# Croduino_Nova_v2_0.net
KiCad netlist of a schematic drawn in EAGLE
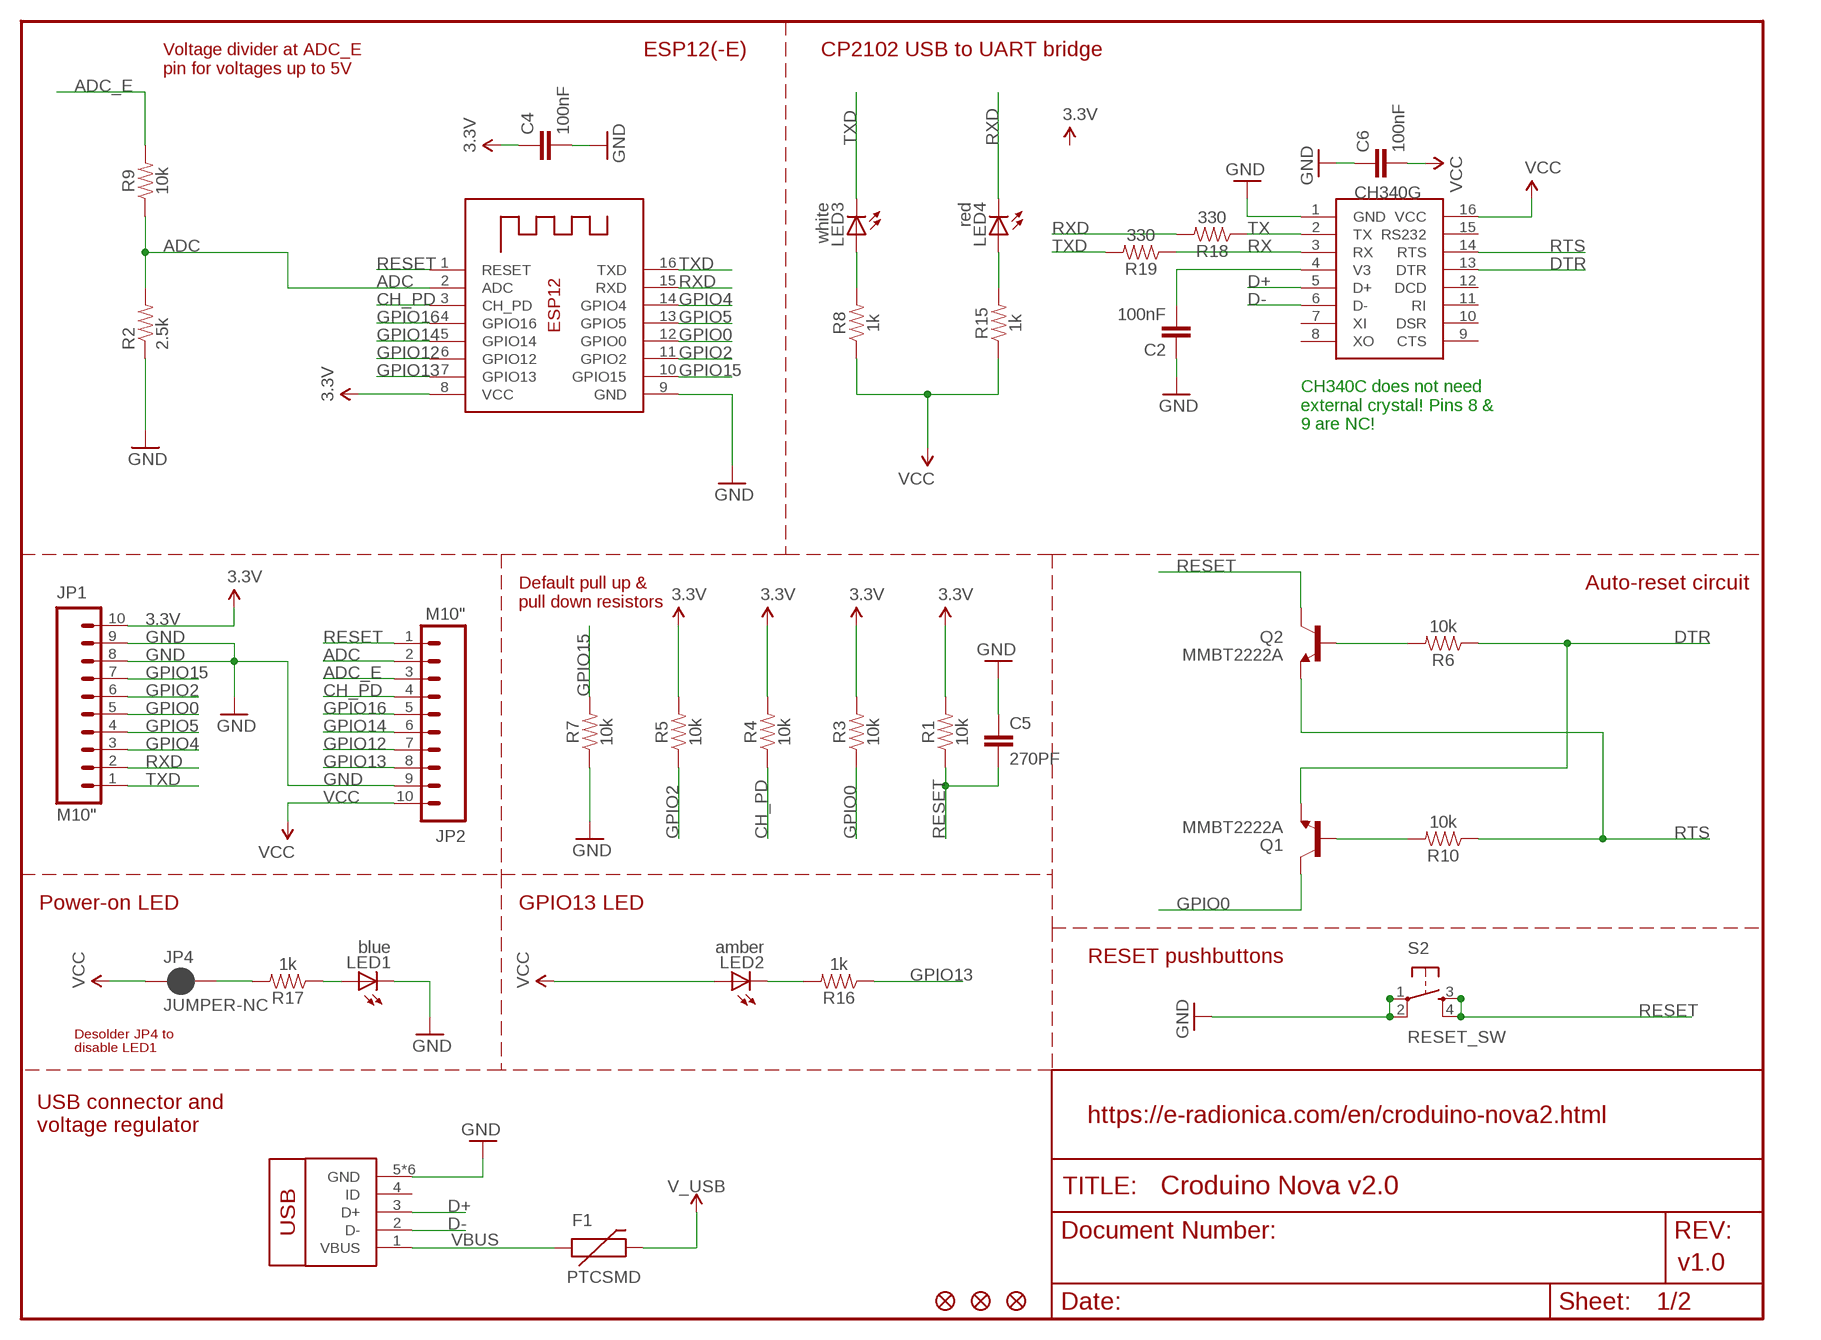
[diagram p0: schematic, sheet 1]
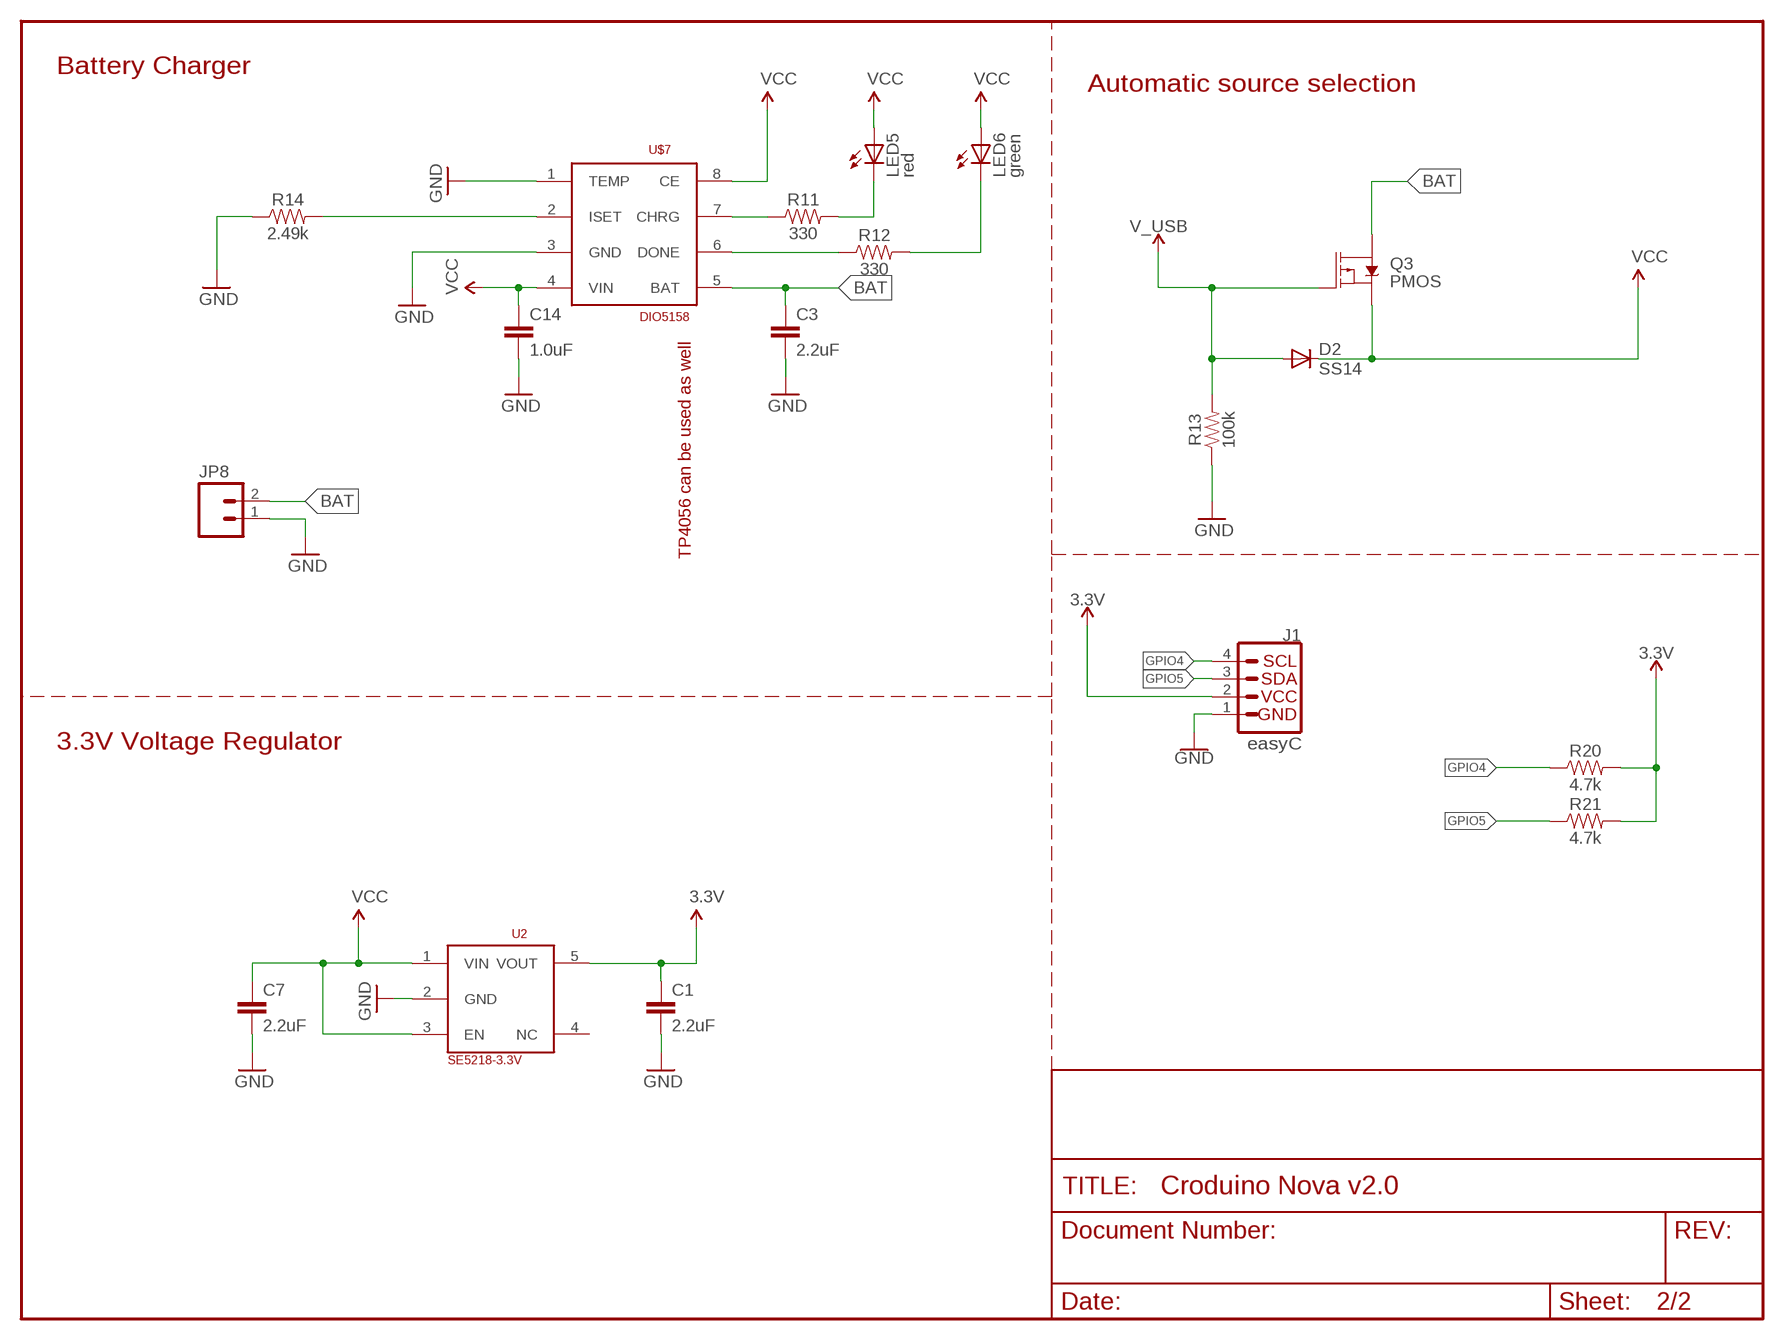
[diagram p1: schematic, sheet 2]

(export (version "E")
  (design (tool "Eeschema 10.0.6"))
  (components
    (comp (ref "C2")
      (value "100nF")
      (footprint "eagle-import:0603-CAP")
      (libsource (lib "eagle-import") (part "CAP0603-CAP"))
    )
    (comp (ref "C4")
      (value "100nF")
      (footprint "eagle-import:0603-CAP")
      (libsource (lib "eagle-import") (part "CAP0603-CAP"))
    )
    (comp (ref "C5")
      (value "270PF")
      (footprint "eagle-import:0603")
      (libsource (lib "eagle-import") (part "270PF-0603-50V-5%"))
    )
    (comp (ref "C6")
      (value "100nF")
      (footprint "eagle-import:0603-CAP")
      (libsource (lib "eagle-import") (part "CAP0603-CAP"))
    )
    (comp (ref "F1")
      (value "PTCSMD")
      (footprint "eagle-import:PTC-1206")
      (libsource (lib "eagle-import") (part "PTCSMD"))
    )
    (comp (ref "JP1")
      (value "M10\"")
      (footprint "eagle-import:1X10")
      (libsource (lib "eagle-import") (part "M10{dblquote}"))
    )
    (comp (ref "JP2")
      (value "M10\"")
      (footprint "eagle-import:1X10")
      (libsource (lib "eagle-import") (part "M10{dblquote}"))
    )
    (comp (ref "JP3")
      (value "FIDUCIAL1X2")
      (footprint "eagle-import:FIDUCIAL-1X2")
      (libsource (lib "eagle-import") (part "FIDUCIAL1X2"))
    )
    (comp (ref "JP4")
      (value "JUMPER-NC")
      (footprint "eagle-import:SMT-JUMPER_2_NC_PASTE_NO-SILK")
      (libsource (lib "eagle-import") (part "JUMPER-SMT_2_NC_PASTE_NO-SILK"))
    )
    (comp (ref "JP5")
      (value "FIDUCIAL1X2")
      (footprint "eagle-import:FIDUCIAL-1X2")
      (libsource (lib "eagle-import") (part "FIDUCIAL1X2"))
    )
    (comp (ref "JP6")
      (value "FIDUCIAL1X2")
      (footprint "eagle-import:FIDUCIAL-1X2")
      (libsource (lib "eagle-import") (part "FIDUCIAL1X2"))
    )
    (comp (ref "LED1")
      (value "blue")
      (footprint "eagle-import:CHIP-LED0805")
      (libsource (lib "eagle-import") (part "LEDCHIP-LED0805"))
    )
    (comp (ref "LED2")
      (value "amber")
      (footprint "eagle-import:CHIP-LED0805")
      (libsource (lib "eagle-import") (part "LEDCHIP-LED0805"))
    )
    (comp (ref "LED3")
      (value "white")
      (footprint "eagle-import:CHIP-LED0805")
      (libsource (lib "eagle-import") (part "LEDCHIP-LED0805"))
    )
    (comp (ref "LED4")
      (value "red")
      (footprint "eagle-import:CHIP-LED0805")
      (libsource (lib "eagle-import") (part "LEDCHIP-LED0805"))
    )
    (comp (ref "Q1")
      (value "MMBT2222A")
      (footprint "eagle-import:SOT23-3")
      (libsource (lib "eagle-import") (part "TRANSISTOR_NPNSOT23-3"))
    )
    (comp (ref "Q2")
      (value "MMBT2222A")
      (footprint "eagle-import:SOT23-3")
      (libsource (lib "eagle-import") (part "TRANSISTOR_NPNSOT23-3"))
    )
    (comp (ref "R1")
      (value "10k")
      (footprint "eagle-import:0603")
      (libsource (lib "eagle-import") (part "10KOHM-0603-1/10W-1%"))
    )
    (comp (ref "R2")
      (value "2.5k")
      (footprint "eagle-import:0603-RES")
      (libsource (lib "eagle-import") (part "RESISTOR0603-RES"))
    )
    (comp (ref "R3")
      (value "10k")
      (footprint "eagle-import:0603")
      (libsource (lib "eagle-import") (part "10KOHM-0603-1/10W-1%"))
    )
    (comp (ref "R4")
      (value "10k")
      (footprint "eagle-import:0603")
      (libsource (lib "eagle-import") (part "10KOHM-0603-1/10W-1%"))
    )
    (comp (ref "R5")
      (value "10k")
      (footprint "eagle-import:0603")
      (libsource (lib "eagle-import") (part "10KOHM-0603-1/10W-1%"))
    )
    (comp (ref "R6")
      (value "10k")
      (footprint "eagle-import:0603")
      (libsource (lib "eagle-import") (part "10KOHM-0603-1/10W-1%"))
    )
    (comp (ref "R7")
      (value "10k")
      (footprint "eagle-import:0603")
      (libsource (lib "eagle-import") (part "10KOHM-0603-1/10W-1%"))
    )
    (comp (ref "R8")
      (value "1k")
      (footprint "eagle-import:0603")
      (libsource (lib "eagle-import") (part "1KOHM-0603-1/10W-1%"))
    )
    (comp (ref "R9")
      (value "10k")
      (footprint "eagle-import:0603")
      (libsource (lib "eagle-import") (part "10KOHM-0603-1/10W-1%"))
    )
    (comp (ref "R10")
      (value "10k")
      (footprint "eagle-import:0603")
      (libsource (lib "eagle-import") (part "10KOHM-0603-1/10W-1%"))
    )
    (comp (ref "R15")
      (value "1k")
      (footprint "eagle-import:0603")
      (libsource (lib "eagle-import") (part "1KOHM-0603-1/10W-1%"))
    )
    (comp (ref "R16")
      (value "1k")
      (footprint "eagle-import:0603")
      (libsource (lib "eagle-import") (part "1KOHM-0603-1/10W-1%"))
    )
    (comp (ref "R17")
      (value "1k")
      (footprint "eagle-import:0603")
      (libsource (lib "eagle-import") (part "1KOHM-0603-1/10W-1%"))
    )
    (comp (ref "R18")
      (value "330")
      (footprint "eagle-import:0603")
      (libsource (lib "eagle-import") (part "1KOHM-0603-1/10W-1%"))
    )
    (comp (ref "R19")
      (value "330")
      (footprint "eagle-import:0603")
      (libsource (lib "eagle-import") (part "1KOHM-0603-1/10W-1%"))
    )
    (comp (ref "S2")
      (value "RESET_SW")
      (footprint "eagle-import:TACTILE_SWITCH_SMD")
      (libsource (lib "eagle-import") (part "TAC_SWITCHSMD"))
    )
    (comp (ref "U$8")
      (value "USB-MICRO")
      (footprint "eagle-import:U-F-M5DD-Y-L")
      (libsource (lib "eagle-import") (part "USB-MICRO"))
    )
    (comp (ref "U$10")
      (value "CH340C")
      (footprint "eagle-import:SOIC16")
      (libsource (lib "eagle-import") (part "CH340G"))
    )
    (comp (ref "X1")
      (value "ESP8266-12")
      (footprint "eagle-import:ESP-12")
      (libsource (lib "eagle-import") (part "ESP-12"))
    )
    (comp (ref "C1")
      (value "2.2uF")
      (footprint "eagle-import:0603")
      (libsource (lib "eagle-import") (part "2.2UF-0603-10V-20%"))
    )
    (comp (ref "C3")
      (value "2.2uF")
      (footprint "eagle-import:0603")
      (libsource (lib "eagle-import") (part "2.2UF-0603-10V-20%"))
    )
    (comp (ref "C7")
      (value "2.2uF")
      (footprint "eagle-import:0603")
      (libsource (lib "eagle-import") (part "2.2UF-0603-10V-20%"))
    )
    (comp (ref "C14")
      (value "1.0uF")
      (footprint "eagle-import:0603")
      (libsource (lib "eagle-import") (part "1.0UF-0603-16V-10%"))
    )
    (comp (ref "D2")
      (value "SS14")
      (footprint "eagle-import:DO-214AC")
      (libsource (lib "eagle-import") (part "DIODE-DO-214AC"))
    )
    (comp (ref "J1")
      (value "QWIIC_CONNECTORJS-1MM")
      (footprint "eagle-import:1X04_1MM_RA")
      (libsource (lib "eagle-import") (part "QWIIC_CONNECTORJS-1MM"))
    )
    (comp (ref "JP8")
      (value "M02-JST-2MM-SMT")
      (footprint "eagle-import:JST-2-SMD")
      (libsource (lib "eagle-import") (part "M02-JST-2MM-SMT"))
    )
    (comp (ref "LED5")
      (value "red")
      (footprint "eagle-import:CHIP-LED0805")
      (libsource (lib "eagle-import") (part "LEDCHIP-LED0805"))
    )
    (comp (ref "LED6")
      (value "green")
      (footprint "eagle-import:CHIP-LED0805")
      (libsource (lib "eagle-import") (part "LEDCHIP-LED0805"))
    )
    (comp (ref "Q3")
      (value "PMOS")
      (footprint "eagle-import:SOT23-3")
      (libsource (lib "eagle-import") (part "MOSFET_PCH-IRLML2244"))
    )
    (comp (ref "R11")
      (value "330")
      (footprint "eagle-import:0603")
      (libsource (lib "eagle-import") (part "150OHM-0603-1/10W-1%"))
    )
    (comp (ref "R12")
      (value "330")
      (footprint "eagle-import:0603")
      (libsource (lib "eagle-import") (part "150OHM-0603-1/10W-1%"))
    )
    (comp (ref "R13")
      (value "100k")
      (footprint "eagle-import:0603")
      (libsource (lib "eagle-import") (part "100KOHM-0603-1/10W-1%"))
    )
    (comp (ref "R14")
      (value "2.49k")
      (footprint "eagle-import:0603")
      (libsource (lib "eagle-import") (part "4.7KOHM-0603-1/10W-1%"))
    )
    (comp (ref "R20")
      (value "4.7k")
      (footprint "eagle-import:0603")
      (libsource (lib "eagle-import") (part "4.7KOHM-0603-1/10W-1%"))
    )
    (comp (ref "R21")
      (value "4.7k")
      (footprint "eagle-import:0603")
      (libsource (lib "eagle-import") (part "4.7KOHM-0603-1/10W-1%"))
    )
    (comp (ref "U$7")
      (value "DIO5158")
      (footprint "eagle-import:SOIC-8")
      (libsource (lib "eagle-import") (part "DIO5158"))
    )
    (comp (ref "U2")
      (value "SE5218-3.3V")
      (footprint "eagle-import:SOT23-5")
      (libsource (lib "eagle-import") (part "SE5218"))
    )
  )
  (nets
    (net (code "1") (name "3.3V") (class "Default")
      (node (ref "C1") (pin "1") (pinfunction "1_1") (pintype "passive"))
      (node (ref "C4") (pin "1") (pinfunction "1_1") (pintype "passive"))
      (node (ref "J1") (pin "2") (pinfunction "2_2") (pintype "power_in"))
      (node (ref "JP1") (pin "10") (pinfunction "10_10") (pintype "passive"))
      (node (ref "R1") (pin "2") (pinfunction "2_2") (pintype "passive"))
      (node (ref "R20") (pin "2") (pinfunction "2_2") (pintype "passive"))
      (node (ref "R21") (pin "2") (pinfunction "2_2") (pintype "passive"))
      (node (ref "R3") (pin "2") (pinfunction "2_2") (pintype "passive"))
      (node (ref "R4") (pin "2") (pinfunction "2_2") (pintype "passive"))
      (node (ref "R5") (pin "2") (pinfunction "2_2") (pintype "passive"))
      (node (ref "U2") (pin "5") (pinfunction "VOUT_5") (pintype "bidirectional"))
      (node (ref "X1") (pin "8") (pinfunction "VCC_8") (pintype "power_in"))
    )
    (net (code "2") (name "ADC") (class "Default")
      (node (ref "JP2") (pin "2") (pinfunction "2_2") (pintype "passive"))
      (node (ref "R2") (pin "2") (pinfunction "2_2") (pintype "passive"))
      (node (ref "R9") (pin "1") (pinfunction "1_1") (pintype "passive"))
      (node (ref "X1") (pin "2") (pinfunction "ADC_2") (pintype "passive"))
    )
    (net (code "3") (name "ADC_E") (class "Default")
      (node (ref "JP2") (pin "3") (pinfunction "3_3") (pintype "passive"))
      (node (ref "R9") (pin "2") (pinfunction "2_2") (pintype "passive"))
    )
    (net (code "4") (name "BAT") (class "Default")
      (node (ref "C3") (pin "1") (pinfunction "1_1") (pintype "passive"))
      (node (ref "JP8") (pin "2") (pinfunction "2_2") (pintype "passive"))
      (node (ref "Q3") (pin "3") (pinfunction "D_3") (pintype "bidirectional"))
      (node (ref "U$7") (pin "5") (pinfunction "BAT_5") (pintype "bidirectional"))
    )
    (net (code "5") (name "CH_PD") (class "Default")
      (node (ref "JP2") (pin "4") (pinfunction "4_4") (pintype "passive"))
      (node (ref "R4") (pin "1") (pinfunction "1_1") (pintype "passive"))
      (node (ref "X1") (pin "3") (pinfunction "CH_PD_3") (pintype "input"))
    )
    (net (code "6") (name "D+") (class "Default")
      (node (ref "U$10") (pin "5") (pinfunction "D+_5") (pintype "bidirectional"))
      (node (ref "U$8") (pin "3") (pinfunction "D+_3") (pintype "bidirectional"))
    )
    (net (code "7") (name "D-") (class "Default")
      (node (ref "U$10") (pin "6") (pinfunction "D-_6") (pintype "bidirectional"))
      (node (ref "U$8") (pin "2") (pinfunction "D-_2") (pintype "bidirectional"))
    )
    (net (code "8") (name "DTR") (class "Default")
      (node (ref "Q1") (pin "2") (pinfunction "E_2") (pintype "passive"))
      (node (ref "R6") (pin "1") (pinfunction "1_1") (pintype "passive"))
      (node (ref "U$10") (pin "13") (pinfunction "DTR_13") (pintype "bidirectional"))
    )
    (net (code "9") (name "GND") (class "Default")
      (node (ref "C1") (pin "2") (pinfunction "2_2") (pintype "passive"))
      (node (ref "C14") (pin "2") (pinfunction "2_2") (pintype "passive"))
      (node (ref "C2") (pin "1") (pinfunction "1_1") (pintype "passive"))
      (node (ref "C3") (pin "2") (pinfunction "2_2") (pintype "passive"))
      (node (ref "C4") (pin "2") (pinfunction "2_2") (pintype "passive"))
      (node (ref "C5") (pin "1") (pinfunction "1_1") (pintype "passive"))
      (node (ref "C6") (pin "1") (pinfunction "1_1") (pintype "passive"))
      (node (ref "C7") (pin "2") (pinfunction "2_2") (pintype "passive"))
      (node (ref "J1") (pin "1") (pinfunction "1_1") (pintype "power_in"))
      (node (ref "JP1") (pin "8") (pinfunction "8_8") (pintype "passive"))
      (node (ref "JP1") (pin "9") (pinfunction "9_9") (pintype "passive"))
      (node (ref "JP2") (pin "9") (pinfunction "9_9") (pintype "passive"))
      (node (ref "JP8") (pin "1") (pinfunction "1_1") (pintype "passive"))
      (node (ref "LED1") (pin "C") (pinfunction "C_C") (pintype "passive"))
      (node (ref "R13") (pin "1") (pinfunction "1_1") (pintype "passive"))
      (node (ref "R14") (pin "1") (pinfunction "1_1") (pintype "passive"))
      (node (ref "R2") (pin "1") (pinfunction "1_1") (pintype "passive"))
      (node (ref "R7") (pin "1") (pinfunction "1_1") (pintype "passive"))
      (node (ref "S2") (pin "1") (pinfunction "1_1") (pintype "passive"))
      (node (ref "S2") (pin "2") (pinfunction "2_2") (pintype "passive"))
      (node (ref "U$10") (pin "1") (pinfunction "GND_1") (pintype "bidirectional"))
      (node (ref "U$7") (pin "1") (pinfunction "TEMP_1") (pintype "bidirectional"))
      (node (ref "U$7") (pin "3") (pinfunction "GND_3") (pintype "bidirectional"))
      (node (ref "U$8") (pin "5") (pinfunction "GND_5") (pintype "bidirectional"))
      (node (ref "U$8") (pin "PAD") (pinfunction "GND_PAD") (pintype "bidirectional"))
      (node (ref "U$8") (pin "SHIELD1") (pinfunction "GND_SHIELD1") (pintype "bidirectional"))
      (node (ref "U$8") (pin "SHIELD2") (pinfunction "GND_SHIELD2") (pintype "bidirectional"))
      (node (ref "U$8") (pin "SHIELD3") (pinfunction "GND_SHIELD3") (pintype "bidirectional"))
      (node (ref "U$8") (pin "SHIELD4") (pinfunction "GND_SHIELD4") (pintype "bidirectional"))
      (node (ref "U2") (pin "2") (pinfunction "GND_2") (pintype "bidirectional"))
      (node (ref "X1") (pin "9") (pinfunction "GND_9") (pintype "power_in"))
    )
    (net (code "10") (name "GPIO0") (class "Default")
      (node (ref "JP1") (pin "5") (pinfunction "5_5") (pintype "passive"))
      (node (ref "Q1") (pin "3") (pinfunction "C_3") (pintype "passive"))
      (node (ref "R3") (pin "1") (pinfunction "1_1") (pintype "passive"))
      (node (ref "X1") (pin "12") (pinfunction "GPIO0_12") (pintype "bidirectional"))
    )
    (net (code "11") (name "GPIO2") (class "Default")
      (node (ref "JP1") (pin "6") (pinfunction "6_6") (pintype "passive"))
      (node (ref "R5") (pin "1") (pinfunction "1_1") (pintype "passive"))
      (node (ref "X1") (pin "11") (pinfunction "GPIO2_11") (pintype "bidirectional"))
    )
    (net (code "12") (name "GPIO4") (class "Default")
      (node (ref "J1") (pin "4") (pinfunction "4_4") (pintype "passive"))
      (node (ref "JP1") (pin "3") (pinfunction "3_3") (pintype "passive"))
      (node (ref "R20") (pin "1") (pinfunction "1_1") (pintype "passive"))
      (node (ref "X1") (pin "14") (pinfunction "GPIO4_14") (pintype "bidirectional"))
    )
    (net (code "13") (name "GPIO5") (class "Default")
      (node (ref "J1") (pin "3") (pinfunction "3_3") (pintype "passive"))
      (node (ref "JP1") (pin "4") (pinfunction "4_4") (pintype "passive"))
      (node (ref "R21") (pin "1") (pinfunction "1_1") (pintype "passive"))
      (node (ref "X1") (pin "13") (pinfunction "GPIO5_13") (pintype "bidirectional"))
    )
    (net (code "14") (name "GPIO12") (class "Default")
      (node (ref "JP2") (pin "7") (pinfunction "7_7") (pintype "passive"))
      (node (ref "X1") (pin "6") (pinfunction "GPIO12_6") (pintype "bidirectional"))
    )
    (net (code "15") (name "GPIO13") (class "Default")
      (node (ref "JP2") (pin "8") (pinfunction "8_8") (pintype "passive"))
      (node (ref "R16") (pin "1") (pinfunction "1_1") (pintype "passive"))
      (node (ref "X1") (pin "7") (pinfunction "GPIO13_7") (pintype "bidirectional"))
    )
    (net (code "16") (name "GPIO14") (class "Default")
      (node (ref "JP2") (pin "6") (pinfunction "6_6") (pintype "passive"))
      (node (ref "X1") (pin "5") (pinfunction "GPIO14_5") (pintype "bidirectional"))
    )
    (net (code "17") (name "GPIO15") (class "Default")
      (node (ref "JP1") (pin "7") (pinfunction "7_7") (pintype "passive"))
      (node (ref "R7") (pin "2") (pinfunction "2_2") (pintype "passive"))
      (node (ref "X1") (pin "10") (pinfunction "GPIO15_10") (pintype "bidirectional"))
    )
    (net (code "18") (name "GPIO16") (class "Default")
      (node (ref "JP2") (pin "5") (pinfunction "5_5") (pintype "passive"))
      (node (ref "X1") (pin "4") (pinfunction "GPIO16_4") (pintype "bidirectional"))
    )
    (net (code "19") (name "Net-(JP4-Pad2)") (class "Default")
      (node (ref "JP4") (pin "2") (pinfunction "2_2") (pintype "passive"))
      (node (ref "R17") (pin "2") (pinfunction "2_2") (pintype "passive"))
    )
    (net (code "20") (name "Net-(LED1-PadA)") (class "Default")
      (node (ref "LED1") (pin "A") (pinfunction "A_A") (pintype "passive"))
      (node (ref "R17") (pin "1") (pinfunction "1_1") (pintype "passive"))
    )
    (net (code "21") (name "Net-(LED2-PadC)") (class "Default")
      (node (ref "LED2") (pin "C") (pinfunction "C_C") (pintype "passive"))
      (node (ref "R16") (pin "2") (pinfunction "2_2") (pintype "passive"))
    )
    (net (code "22") (name "Net-(LED3-PadA)") (class "Default")
      (node (ref "LED3") (pin "A") (pinfunction "A_A") (pintype "passive"))
      (node (ref "R8") (pin "2") (pinfunction "2_2") (pintype "passive"))
    )
    (net (code "23") (name "Net-(LED4-PadA)") (class "Default")
      (node (ref "LED4") (pin "A") (pinfunction "A_A") (pintype "passive"))
      (node (ref "R15") (pin "2") (pinfunction "2_2") (pintype "passive"))
    )
    (net (code "24") (name "Net-(LED5-PadC)") (class "Default")
      (node (ref "LED5") (pin "C") (pinfunction "C_C") (pintype "passive"))
      (node (ref "R11") (pin "2") (pinfunction "2_2") (pintype "passive"))
    )
    (net (code "25") (name "Net-(LED6-PadC)") (class "Default")
      (node (ref "LED6") (pin "C") (pinfunction "C_C") (pintype "passive"))
      (node (ref "R12") (pin "2") (pinfunction "2_2") (pintype "passive"))
    )
    (net (code "26") (name "Net-(Q1-B)") (class "Default")
      (node (ref "Q1") (pin "1") (pinfunction "B_1") (pintype "passive"))
      (node (ref "R10") (pin "2") (pinfunction "2_2") (pintype "passive"))
    )
    (net (code "27") (name "Net-(Q2-B)") (class "Default")
      (node (ref "Q2") (pin "1") (pinfunction "B_1") (pintype "passive"))
      (node (ref "R6") (pin "2") (pinfunction "2_2") (pintype "passive"))
    )
    (net (code "28") (name "Net-(U$7-CHRG)") (class "Default")
      (node (ref "R11") (pin "1") (pinfunction "1_1") (pintype "passive"))
      (node (ref "U$7") (pin "7") (pinfunction "CHRG_7") (pintype "bidirectional"))
    )
    (net (code "29") (name "Net-(U$7-DONE)") (class "Default")
      (node (ref "R12") (pin "1") (pinfunction "1_1") (pintype "passive"))
      (node (ref "U$7") (pin "6") (pinfunction "DONE_6") (pintype "bidirectional"))
    )
    (net (code "30") (name "Net-(U$7-ISET)") (class "Default")
      (node (ref "R14") (pin "2") (pinfunction "2_2") (pintype "passive"))
      (node (ref "U$7") (pin "2") (pinfunction "ISET_2") (pintype "bidirectional"))
    )
    (net (code "31") (name "Net-(U$10-V3)") (class "Default")
      (node (ref "C2") (pin "2") (pinfunction "2_2") (pintype "passive"))
      (node (ref "U$10") (pin "4") (pinfunction "V3_4") (pintype "bidirectional"))
    )
    (net (code "32") (name "RESET") (class "Default")
      (node (ref "C5") (pin "2") (pinfunction "2_2") (pintype "passive"))
      (node (ref "JP2") (pin "1") (pinfunction "1_1") (pintype "passive"))
      (node (ref "Q2") (pin "3") (pinfunction "C_3") (pintype "passive"))
      (node (ref "R1") (pin "1") (pinfunction "1_1") (pintype "passive"))
      (node (ref "S2") (pin "3") (pinfunction "3_3") (pintype "passive"))
      (node (ref "S2") (pin "4") (pinfunction "4_4") (pintype "passive"))
      (node (ref "X1") (pin "1") (pinfunction "RESET_1") (pintype "input"))
    )
    (net (code "33") (name "RTS") (class "Default")
      (node (ref "Q2") (pin "2") (pinfunction "E_2") (pintype "passive"))
      (node (ref "R10") (pin "1") (pinfunction "1_1") (pintype "passive"))
      (node (ref "U$10") (pin "14") (pinfunction "RTS_14") (pintype "bidirectional"))
    )
    (net (code "34") (name "RX") (class "Default")
      (node (ref "R19") (pin "1") (pinfunction "1_1") (pintype "passive"))
      (node (ref "U$10") (pin "3") (pinfunction "RX_3") (pintype "bidirectional"))
    )
    (net (code "35") (name "RXD") (class "Default")
      (node (ref "JP1") (pin "2") (pinfunction "2_2") (pintype "passive"))
      (node (ref "LED4") (pin "C") (pinfunction "C_C") (pintype "passive"))
      (node (ref "R18") (pin "2") (pinfunction "2_2") (pintype "passive"))
      (node (ref "X1") (pin "15") (pinfunction "RXD_15") (pintype "input"))
    )
    (net (code "36") (name "TX") (class "Default")
      (node (ref "R18") (pin "1") (pinfunction "1_1") (pintype "passive"))
      (node (ref "U$10") (pin "2") (pinfunction "TX_2") (pintype "bidirectional"))
    )
    (net (code "37") (name "TXD") (class "Default")
      (node (ref "JP1") (pin "1") (pinfunction "1_1") (pintype "passive"))
      (node (ref "LED3") (pin "C") (pinfunction "C_C") (pintype "passive"))
      (node (ref "R19") (pin "2") (pinfunction "2_2") (pintype "passive"))
      (node (ref "X1") (pin "16") (pinfunction "TXD_16") (pintype "output"))
    )
    (net (code "38") (name "VBUS") (class "Default")
      (node (ref "F1") (pin "1") (pinfunction "1_1") (pintype "bidirectional"))
      (node (ref "U$8") (pin "1") (pinfunction "VBUS_1") (pintype "bidirectional"))
    )
    (net (code "39") (name "VCC") (class "Default")
      (node (ref "C14") (pin "1") (pinfunction "1_1") (pintype "passive"))
      (node (ref "C6") (pin "2") (pinfunction "2_2") (pintype "passive"))
      (node (ref "C7") (pin "1") (pinfunction "1_1") (pintype "passive"))
      (node (ref "D2") (pin "C") (pinfunction "C_C") (pintype "passive"))
      (node (ref "JP2") (pin "10") (pinfunction "10_10") (pintype "passive"))
      (node (ref "JP4") (pin "1") (pinfunction "1_1") (pintype "passive"))
      (node (ref "LED2") (pin "A") (pinfunction "A_A") (pintype "passive"))
      (node (ref "LED5") (pin "A") (pinfunction "A_A") (pintype "passive"))
      (node (ref "LED6") (pin "A") (pinfunction "A_A") (pintype "passive"))
      (node (ref "Q3") (pin "2") (pinfunction "S_2") (pintype "bidirectional"))
      (node (ref "R15") (pin "1") (pinfunction "1_1") (pintype "passive"))
      (node (ref "R8") (pin "1") (pinfunction "1_1") (pintype "passive"))
      (node (ref "U$10") (pin "16") (pinfunction "VCC_16") (pintype "bidirectional"))
      (node (ref "U$7") (pin "4") (pinfunction "VIN_4") (pintype "bidirectional"))
      (node (ref "U$7") (pin "8") (pinfunction "CE_8") (pintype "bidirectional"))
      (node (ref "U2") (pin "1") (pinfunction "VIN_1") (pintype "bidirectional"))
      (node (ref "U2") (pin "3") (pinfunction "EN_3") (pintype "bidirectional"))
    )
    (net (code "40") (name "V_USB") (class "Default")
      (node (ref "D2") (pin "A") (pinfunction "A_A") (pintype "passive"))
      (node (ref "F1") (pin "2") (pinfunction "2_2") (pintype "bidirectional"))
      (node (ref "Q3") (pin "1") (pinfunction "G_1") (pintype "bidirectional"))
      (node (ref "R13") (pin "2") (pinfunction "2_2") (pintype "passive"))
    )
    (net (code "41") (name "unconnected-(U$8-ID-Pad4)") (class "Default")
      (node (ref "U$8") (pin "4") (pinfunction "ID_4") (pintype "bidirectional"))
    )
    (net (code "42") (name "unconnected-(U$10-CTS-Pad9)") (class "Default")
      (node (ref "U$10") (pin "9") (pinfunction "CTS_9") (pintype "bidirectional"))
    )
    (net (code "43") (name "unconnected-(U$10-DCD-Pad12)") (class "Default")
      (node (ref "U$10") (pin "12") (pinfunction "DCD_12") (pintype "bidirectional"))
    )
    (net (code "44") (name "unconnected-(U$10-DSR-Pad10)") (class "Default")
      (node (ref "U$10") (pin "10") (pinfunction "DSR_10") (pintype "bidirectional"))
    )
    (net (code "45") (name "unconnected-(U$10-RI-Pad11)") (class "Default")
      (node (ref "U$10") (pin "11") (pinfunction "RI_11") (pintype "bidirectional"))
    )
    (net (code "46") (name "unconnected-(U$10-RS232-Pad15)") (class "Default")
      (node (ref "U$10") (pin "15") (pinfunction "RS232_15") (pintype "bidirectional"))
    )
    (net (code "47") (name "unconnected-(U$10-XI-Pad7)") (class "Default")
      (node (ref "U$10") (pin "7") (pinfunction "XI_7") (pintype "bidirectional"))
    )
    (net (code "48") (name "unconnected-(U$10-XO-Pad8)") (class "Default")
      (node (ref "U$10") (pin "8") (pinfunction "XO_8") (pintype "bidirectional"))
    )
    (net (code "49") (name "unconnected-(U2-NC-Pad4)") (class "Default")
      (node (ref "U2") (pin "4") (pinfunction "NC_4") (pintype "bidirectional"))
    )
  )
)
